# kuramoto6.net
KiCad netlist of a schematic drawn in EAGLE
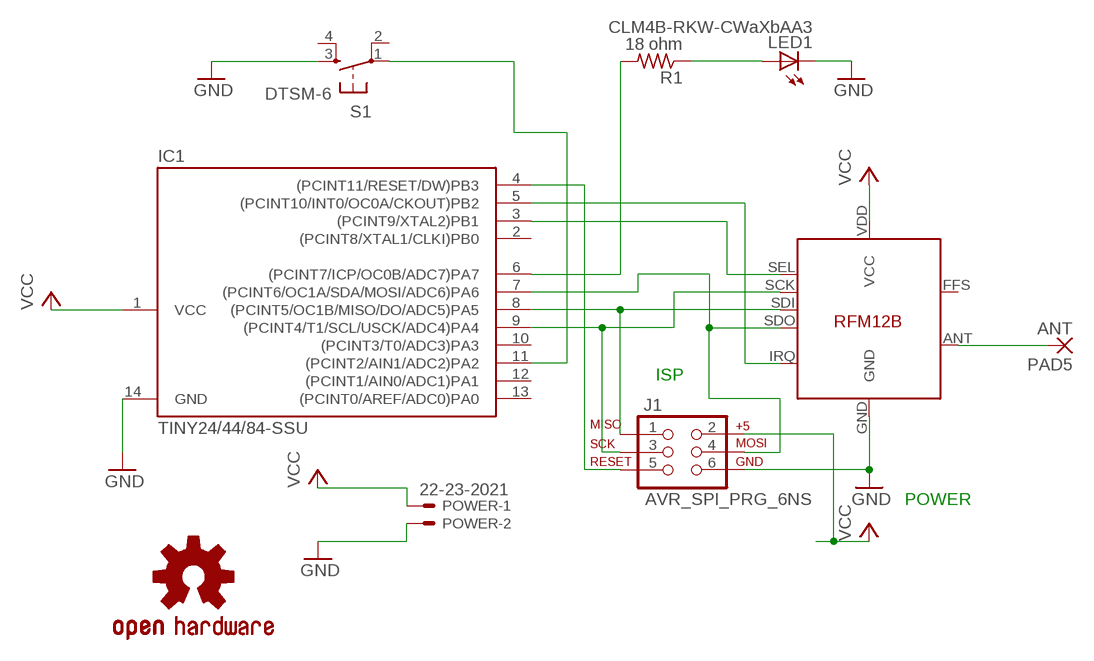
[diagram p0: schematic, sheet 1]

(export (version "E")
  (design (tool "Eeschema 10.0.6"))
  (components
    (comp (ref "IC1")
      (value "TINY24/44/84-SSU")
      (footprint "eagle-import:SOIC14")
      (libsource (lib "eagle-import") (part "TINY24/44/84-SSU"))
    )
    (comp (ref "J1")
      (value "AVR_SPI_PRG_6NS")
      (footprint "eagle-import:2X3-NS")
      (libsource (lib "eagle-import") (part "AVR_SPI_PRG_6NS"))
    )
    (comp (ref "LED1")
      (value "CLM4B-RKW-CWaXbAA3")
      (footprint "eagle-import:P-LCC-4")
      (libsource (lib "eagle-import") (part "LEDP-LCC-4"))
    )
    (comp (ref "PAD5")
      (value "ANT")
      (footprint "eagle-import:2,54_1,0")
      (libsource (lib "eagle-import") (part "WIREPAD2,54/1,0"))
    )
    (comp (ref "POWER")
      (value "22-23-2021")
      (footprint "eagle-import:22-23-2021")
      (fields (field (name "MF") "MOLEX"))
      (libsource (lib "eagle-import") (part "22-23-2021"))
    )
    (comp (ref "R1")
      (value "18 ohm")
      (footprint "eagle-import:R0805")
      (libsource (lib "eagle-import") (part "R-US_R0805"))
    )
    (comp (ref "RFM12B")
      (value "RFM12BN")
      (footprint "eagle-import:RFM12B-NARROW")
      (libsource (lib "eagle-import") (part "RFM12BN"))
    )
    (comp (ref "S1")
      (value "DTSM-6")
      (footprint "eagle-import:DTSM-6")
      (libsource (lib "eagle-import") (part "DTSM-6"))
    )
    (comp (ref "U$1")
      (value "OSHW-LOGOS")
      (footprint "eagle-import:OSHW-LOGO-S")
      (libsource (lib "eagle-import") (part "OSHW-LOGOS"))
    )
  )
  (nets
    (net (code "1") (name "GND") (class "Default")
      (node (ref "IC1") (pin "14") (pinfunction "GND_14") (pintype "power_in"))
      (node (ref "J1") (pin "6") (pinfunction "6_6") (pintype "passive"))
      (node (ref "LED1") (pin "C@4") (pinfunction "C_C@4") (pintype "passive"))
      (node (ref "POWER") (pin "2") (pinfunction "S_2") (pintype "passive"))
      (node (ref "RFM12B") (pin "GND") (pinfunction "GND_GND") (pintype "power_in"))
      (node (ref "S1") (pin "3") (pinfunction "3_3") (pintype "passive"))
    )
    (net (code "2") (name "Net-(IC1-(PCINT2{slash}AIN1{slash}ADC2)PA2)") (class "Default")
      (node (ref "IC1") (pin "11") (pinfunction "(PCINT2/AIN1/ADC2)PA2_11") (pintype "bidirectional"))
      (node (ref "S1") (pin "1") (pinfunction "1_1") (pintype "passive"))
    )
    (net (code "3") (name "Net-(IC1-(PCINT4{slash}T1{slash}SCL{slash}USCK{slash}ADC4)PA4)") (class "Default")
      (node (ref "IC1") (pin "9") (pinfunction "(PCINT4/T1/SCL/USCK/ADC4)PA4_9") (pintype "bidirectional"))
      (node (ref "J1") (pin "3") (pinfunction "3_3") (pintype "passive"))
      (node (ref "RFM12B") (pin "SCK") (pinfunction "SCK_SCK") (pintype "input"))
    )
    (net (code "4") (name "Net-(IC1-(PCINT5{slash}OC1B{slash}MISO{slash}DO{slash}ADC5)PA5)") (class "Default")
      (node (ref "IC1") (pin "8") (pinfunction "(PCINT5/OC1B/MISO/DO/ADC5)PA5_8") (pintype "bidirectional"))
      (node (ref "J1") (pin "1") (pinfunction "1_1") (pintype "passive"))
      (node (ref "RFM12B") (pin "SDI") (pinfunction "SDI_SDI") (pintype "input"))
    )
    (net (code "5") (name "Net-(IC1-(PCINT6{slash}OC1A{slash}SDA{slash}MOSI{slash}ADC6)PA6)") (class "Default")
      (node (ref "IC1") (pin "7") (pinfunction "(PCINT6/OC1A/SDA/MOSI/ADC6)PA6_7") (pintype "bidirectional"))
      (node (ref "J1") (pin "4") (pinfunction "4_4") (pintype "passive"))
      (node (ref "RFM12B") (pin "SDO") (pinfunction "SDO_SDO") (pintype "output"))
    )
    (net (code "6") (name "Net-(IC1-(PCINT7{slash}ICP{slash}OC0B{slash}ADC7)PA7)") (class "Default")
      (node (ref "IC1") (pin "6") (pinfunction "(PCINT7/ICP/OC0B/ADC7)PA7_6") (pintype "bidirectional"))
      (node (ref "R1") (pin "2") (pinfunction "2_2") (pintype "passive"))
    )
    (net (code "7") (name "Net-(IC1-(PCINT9{slash}XTAL2)PB1)") (class "Default")
      (node (ref "IC1") (pin "3") (pinfunction "(PCINT9/XTAL2)PB1_3") (pintype "bidirectional"))
      (node (ref "RFM12B") (pin "SEL") (pinfunction "SEL_SEL") (pintype "input"))
    )
    (net (code "8") (name "Net-(IC1-(PCINT10{slash}INT0{slash}OC0A{slash}CKOUT)PB2)") (class "Default")
      (node (ref "IC1") (pin "5") (pinfunction "(PCINT10/INT0/OC0A/CKOUT)PB2_5") (pintype "bidirectional"))
      (node (ref "RFM12B") (pin "IRQ") (pinfunction "IRQ_IRQ") (pintype "open_collector"))
    )
    (net (code "9") (name "Net-(IC1-(PCINT11{slash}RESET{slash}DW)PB3)") (class "Default")
      (node (ref "IC1") (pin "4") (pinfunction "(PCINT11/RESET/DW)PB3_4") (pintype "bidirectional"))
      (node (ref "J1") (pin "5") (pinfunction "5_5") (pintype "passive"))
    )
    (net (code "10") (name "Net-(LED1-PadA)") (class "Default")
      (node (ref "LED1") (pin "A") (pinfunction "A_A") (pintype "passive"))
      (node (ref "R1") (pin "1") (pinfunction "1_1") (pintype "passive"))
    )
    (net (code "11") (name "Net-(PAD5-P)") (class "Default")
      (node (ref "PAD5") (pin "1") (pinfunction "P_1") (pintype "passive"))
      (node (ref "RFM12B") (pin "ANT") (pinfunction "ANT_ANT") (pintype "passive"))
    )
    (net (code "12") (name "VCC") (class "Default")
      (node (ref "IC1") (pin "1") (pinfunction "VCC_1") (pintype "power_in"))
      (node (ref "J1") (pin "2") (pinfunction "2_2") (pintype "passive"))
      (node (ref "POWER") (pin "1") (pinfunction "S_1") (pintype "passive"))
      (node (ref "RFM12B") (pin "VDD") (pinfunction "VCC_VDD") (pintype "power_in"))
    )
    (net (code "13") (name "unconnected-(IC1-(PCINT0{slash}AREF{slash}ADC0)PA0-Pad13)") (class "Default")
      (node (ref "IC1") (pin "13") (pinfunction "(PCINT0/AREF/ADC0)PA0_13") (pintype "bidirectional"))
    )
    (net (code "14") (name "unconnected-(IC1-(PCINT1{slash}AIN0{slash}ADC1)PA1-Pad12)") (class "Default")
      (node (ref "IC1") (pin "12") (pinfunction "(PCINT1/AIN0/ADC1)PA1_12") (pintype "bidirectional"))
    )
    (net (code "15") (name "unconnected-(IC1-(PCINT3{slash}T0{slash}ADC3)PA3-Pad10)") (class "Default")
      (node (ref "IC1") (pin "10") (pinfunction "(PCINT3/T0/ADC3)PA3_10") (pintype "bidirectional"))
    )
    (net (code "16") (name "unconnected-(IC1-(PCINT8{slash}XTAL1{slash}CLKI)PB0-Pad2)") (class "Default")
      (node (ref "IC1") (pin "2") (pinfunction "(PCINT8/XTAL1/CLKI)PB0_2") (pintype "bidirectional"))
    )
    (net (code "17") (name "unconnected-(RFM12B-PadFFS)") (class "Default")
      (node (ref "RFM12B") (pin "FFS") (pinfunction "FFS_FFS") (pintype "bidirectional"))
    )
    (net (code "18") (name "unconnected-(S1-Pad2)") (class "Default")
      (node (ref "S1") (pin "2") (pinfunction "2_2") (pintype "passive"))
    )
    (net (code "19") (name "unconnected-(S1-Pad4)") (class "Default")
      (node (ref "S1") (pin "4") (pinfunction "4_4") (pintype "passive"))
    )
  )
)
